# Microcontroller.net
KiCad netlist of a schematic drawn in Altium Designer
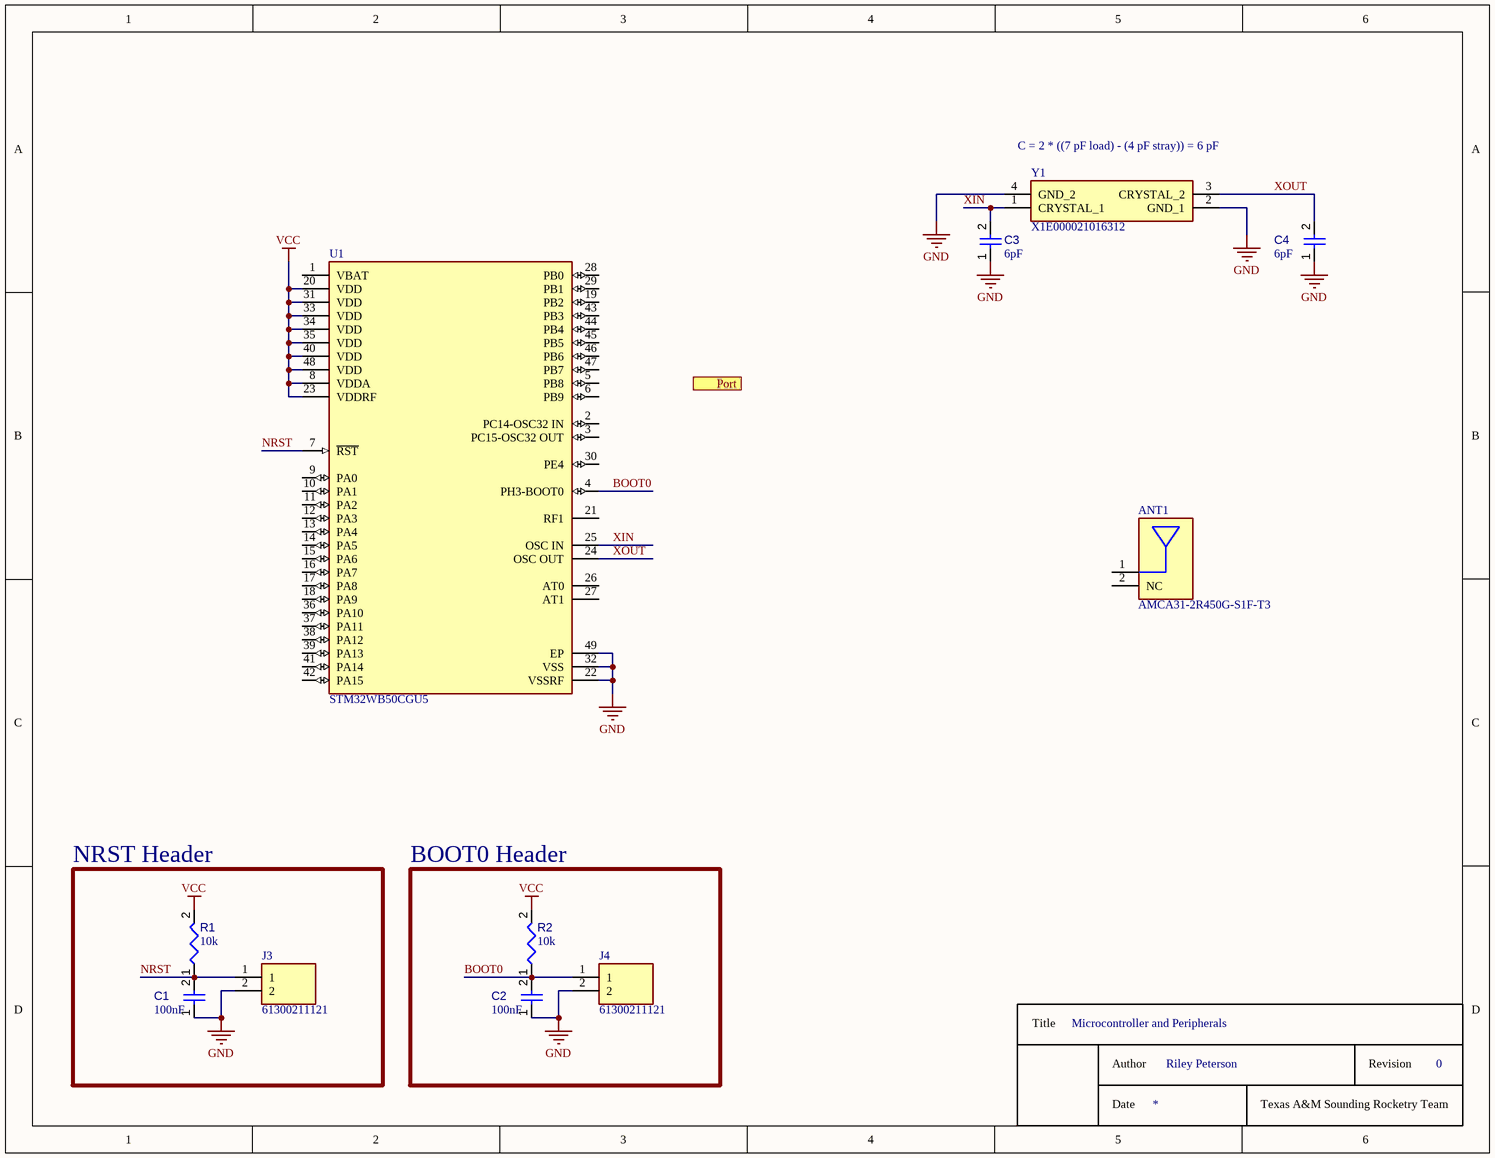
[diagram p0: Microcontroller.SchDoc]

(export (version "E")
  (design (tool "Eeschema 10.0.6"))
  (components
    (comp (ref "ANT1")
      (value "AMCA31-2R450G-S1F-T3")
      (footprint "FP-AMCA31-MFG")
      (description "RF ANT 2.4GHZ CHIP SOLDER SMD")
      (fields
        (field (name "OCTOPART") "https://octopart.com/amca31-2r450g-s1f-t3-abracon-31435383")
        (field (name "MANUFACTURER") "Abracon")
      )
      (libsource (lib "Altium Content Vault") (part "feefd54aed95757a858c12fc87bd8d5"))
    )
    (comp (ref "C1")
      (value "100nF")
      (footprint "CAPC0603(1608)100_L")
      (description "Capacitor")
      (fields (field (name "Comment") "Capacitors,0603,smt,100nF"))
      (libsource (lib "Riley Peterson") (part "CAP-NP-2"))
    )
    (comp (ref "C2")
      (value "100nF")
      (footprint "CAPC0603(1608)100_L")
      (description "Capacitor")
      (fields (field (name "Comment") "Capacitors,0603,smt,100nF"))
      (libsource (lib "Riley Peterson") (part "CAP-NP-2"))
    )
    (comp (ref "C3")
      (value "6pF")
      (footprint "CAPC0603(1608)100_L")
      (description "Capacitor")
      (fields (field (name "Comment") "Capacitors,0603,smt,6pF"))
      (libsource (lib "Riley Peterson") (part "CAP-NP-2"))
    )
    (comp (ref "C4")
      (value "6pF")
      (footprint "CAPC0603(1608)100_L")
      (description "Capacitor")
      (fields (field (name "Comment") "Capacitors,0603,smt,6pF"))
      (libsource (lib "Riley Peterson") (part "CAP-NP-2"))
    )
    (comp (ref "J3")
      (value "61300211121")
      (footprint "SamacSys:HDRV2W110P0X254_1X2_508X254X854P")
      (description "Connector")
      (fields (field (name "MOUSER PART NUMBER") "710-61300211121"))
      (libsource (lib "*") (part "61300211121"))
    )
    (comp (ref "J4")
      (value "61300211121")
      (footprint "SamacSys:HDRV2W110P0X254_1X2_508X254X854P")
      (description "Connector")
      (fields (field (name "MOUSER PART NUMBER") "710-61300211121"))
      (libsource (lib "*") (part "61300211121"))
    )
    (comp (ref "R1")
      (value "10k")
      (footprint "RESC0603(1608)_L")
      (description "Resistor")
      (fields (field (name "Comment") "Resistors,0603,smt,10k"))
      (libsource (lib "Riley Peterson") (part "RES-2"))
    )
    (comp (ref "R2")
      (value "10k")
      (footprint "RESC0603(1608)_L")
      (description "Resistor")
      (fields (field (name "Comment") "Resistors,0603,smt,10k"))
      (libsource (lib "Riley Peterson") (part "RES-2"))
    )
    (comp (ref "U1")
      (value "STM32WB50CGU5")
      (footprint "FP-UFQFPN48-A0B9-MFG")
      (description "ULTRA-LOW-POWER DUAL CORE ARM CO")
      (fields
        (field (name "MANUFACTURER") "STMicroelectronics")
        (field (name "OCTOPART") "https://octopart.com/stm32wb50cgu5-stmicroelectronics-106131324")
      )
      (libsource (lib "Altium Content Vault") (part "0a46fecf8989bdbed877c0c59f49bea"))
    )
    (comp (ref "Y1")
      (value "X1E000021016312")
      (footprint "SamacSys:X1E000021016312")
      (description "Crystal or Oscillator")
      (libsource (lib "*") (part "X1E000021016312"))
    )
  )
  (nets
    (net (code "1") (name "/BOOT0") (class "Default")
      (node (ref "C2") (pin "2") (pinfunction "2_2") (pintype "passive"))
      (node (ref "J4") (pin "1") (pinfunction "1_1") (pintype "passive"))
      (node (ref "R2") (pin "1") (pinfunction "1_1") (pintype "passive"))
      (node (ref "U1") (pin "4") (pinfunction "PH3-BOOT0_4") (pintype "bidirectional"))
    )
    (net (code "2") (name "/NRST") (class "Default")
      (node (ref "C1") (pin "2") (pinfunction "2_2") (pintype "passive"))
      (node (ref "J3") (pin "1") (pinfunction "1_1") (pintype "passive"))
      (node (ref "R1") (pin "1") (pinfunction "1_1") (pintype "passive"))
      (node (ref "U1") (pin "7") (pinfunction "~{RST}_7") (pintype "input"))
    )
    (net (code "4") (name "/XIN") (class "Default")
      (node (ref "C3") (pin "2") (pinfunction "2_2") (pintype "passive"))
      (node (ref "U1") (pin "25") (pinfunction "OSC_IN_25") (pintype "passive"))
      (node (ref "Y1") (pin "1") (pinfunction "CRYSTAL_1_1") (pintype "passive"))
    )
    (net (code "5") (name "/XOUT") (class "Default")
      (node (ref "C4") (pin "2") (pinfunction "2_2") (pintype "passive"))
      (node (ref "U1") (pin "24") (pinfunction "OSC_OUT_24") (pintype "passive"))
      (node (ref "Y1") (pin "3") (pinfunction "CRYSTAL_2_3") (pintype "passive"))
    )
    (net (code "6") (name "GND") (class "Default")
      (node (ref "C1") (pin "1") (pinfunction "1_1") (pintype "passive"))
      (node (ref "C2") (pin "1") (pinfunction "1_1") (pintype "passive"))
      (node (ref "C3") (pin "1") (pinfunction "1_1") (pintype "passive"))
      (node (ref "C4") (pin "1") (pinfunction "1_1") (pintype "passive"))
      (node (ref "J3") (pin "2") (pinfunction "2_2") (pintype "passive"))
      (node (ref "J4") (pin "2") (pinfunction "2_2") (pintype "passive"))
      (node (ref "U1") (pin "22") (pinfunction "VSSRF_22") (pintype "power_in"))
      (node (ref "U1") (pin "32") (pinfunction "VSS_32") (pintype "power_in"))
      (node (ref "U1") (pin "49") (pinfunction "EP_49") (pintype "power_in"))
      (node (ref "Y1") (pin "2") (pinfunction "GND_1_2") (pintype "passive"))
      (node (ref "Y1") (pin "4") (pinfunction "GND_2_4") (pintype "passive"))
    )
    (net (code "7") (name "VCC") (class "Default")
      (node (ref "R1") (pin "2") (pinfunction "2_2") (pintype "passive"))
      (node (ref "R2") (pin "2") (pinfunction "2_2") (pintype "passive"))
      (node (ref "U1") (pin "20") (pinfunction "VDD_20") (pintype "power_in"))
      (node (ref "U1") (pin "23") (pinfunction "VDDRF_23") (pintype "power_in"))
      (node (ref "U1") (pin "31") (pinfunction "VDD_31") (pintype "power_in"))
      (node (ref "U1") (pin "33") (pinfunction "VDD_33") (pintype "power_in"))
      (node (ref "U1") (pin "34") (pinfunction "VDD_34") (pintype "power_in"))
      (node (ref "U1") (pin "35") (pinfunction "VDD_35") (pintype "power_in"))
      (node (ref "U1") (pin "40") (pinfunction "VDD_40") (pintype "power_in"))
      (node (ref "U1") (pin "48") (pinfunction "VDD_48") (pintype "power_in"))
      (node (ref "U1") (pin "8") (pinfunction "VDDA_8") (pintype "power_in"))
    )
    (net (code "8") (name "unconnected-(ANT1-Feed_Point-Pad1)") (class "Default")
      (node (ref "ANT1") (pin "1") (pinfunction "Feed_Point_1") (pintype "passive"))
    )
    (net (code "9") (name "unconnected-(ANT1-NC-Pad2)") (class "Default")
      (node (ref "ANT1") (pin "2") (pinfunction "NC_2") (pintype "passive"))
    )
    (net (code "10") (name "unconnected-(U1-AT0-Pad26)") (class "Default")
      (node (ref "U1") (pin "26") (pinfunction "AT0_26") (pintype "passive"))
    )
    (net (code "11") (name "unconnected-(U1-AT1-Pad27)") (class "Default")
      (node (ref "U1") (pin "27") (pinfunction "AT1_27") (pintype "passive"))
    )
    (net (code "12") (name "unconnected-(U1-PA0-Pad9)") (class "Default")
      (node (ref "U1") (pin "9") (pinfunction "PA0_9") (pintype "bidirectional"))
    )
    (net (code "13") (name "unconnected-(U1-PA1-Pad10)") (class "Default")
      (node (ref "U1") (pin "10") (pinfunction "PA1_10") (pintype "bidirectional"))
    )
    (net (code "14") (name "unconnected-(U1-PA2-Pad11)") (class "Default")
      (node (ref "U1") (pin "11") (pinfunction "PA2_11") (pintype "bidirectional"))
    )
    (net (code "15") (name "unconnected-(U1-PA3-Pad12)") (class "Default")
      (node (ref "U1") (pin "12") (pinfunction "PA3_12") (pintype "bidirectional"))
    )
    (net (code "16") (name "unconnected-(U1-PA4-Pad13)") (class "Default")
      (node (ref "U1") (pin "13") (pinfunction "PA4_13") (pintype "bidirectional"))
    )
    (net (code "17") (name "unconnected-(U1-PA5-Pad14)") (class "Default")
      (node (ref "U1") (pin "14") (pinfunction "PA5_14") (pintype "bidirectional"))
    )
    (net (code "18") (name "unconnected-(U1-PA6-Pad15)") (class "Default")
      (node (ref "U1") (pin "15") (pinfunction "PA6_15") (pintype "bidirectional"))
    )
    (net (code "19") (name "unconnected-(U1-PA7-Pad16)") (class "Default")
      (node (ref "U1") (pin "16") (pinfunction "PA7_16") (pintype "bidirectional"))
    )
    (net (code "20") (name "unconnected-(U1-PA8-Pad17)") (class "Default")
      (node (ref "U1") (pin "17") (pinfunction "PA8_17") (pintype "bidirectional"))
    )
    (net (code "21") (name "unconnected-(U1-PA9-Pad18)") (class "Default")
      (node (ref "U1") (pin "18") (pinfunction "PA9_18") (pintype "bidirectional"))
    )
    (net (code "22") (name "unconnected-(U1-PA10-Pad36)") (class "Default")
      (node (ref "U1") (pin "36") (pinfunction "PA10_36") (pintype "bidirectional"))
    )
    (net (code "23") (name "unconnected-(U1-PA11-Pad37)") (class "Default")
      (node (ref "U1") (pin "37") (pinfunction "PA11_37") (pintype "bidirectional"))
    )
    (net (code "24") (name "unconnected-(U1-PA12-Pad38)") (class "Default")
      (node (ref "U1") (pin "38") (pinfunction "PA12_38") (pintype "bidirectional"))
    )
    (net (code "25") (name "unconnected-(U1-PA13-Pad39)") (class "Default")
      (node (ref "U1") (pin "39") (pinfunction "PA13_39") (pintype "bidirectional"))
    )
    (net (code "26") (name "unconnected-(U1-PA14-Pad41)") (class "Default")
      (node (ref "U1") (pin "41") (pinfunction "PA14_41") (pintype "bidirectional"))
    )
    (net (code "27") (name "unconnected-(U1-PA15-Pad42)") (class "Default")
      (node (ref "U1") (pin "42") (pinfunction "PA15_42") (pintype "bidirectional"))
    )
    (net (code "28") (name "unconnected-(U1-PB0-Pad28)") (class "Default")
      (node (ref "U1") (pin "28") (pinfunction "PB0_28") (pintype "bidirectional"))
    )
    (net (code "29") (name "unconnected-(U1-PB1-Pad29)") (class "Default")
      (node (ref "U1") (pin "29") (pinfunction "PB1_29") (pintype "bidirectional"))
    )
    (net (code "30") (name "unconnected-(U1-PB2-Pad19)") (class "Default")
      (node (ref "U1") (pin "19") (pinfunction "PB2_19") (pintype "bidirectional"))
    )
    (net (code "31") (name "unconnected-(U1-PB3-Pad43)") (class "Default")
      (node (ref "U1") (pin "43") (pinfunction "PB3_43") (pintype "bidirectional"))
    )
    (net (code "32") (name "unconnected-(U1-PB4-Pad44)") (class "Default")
      (node (ref "U1") (pin "44") (pinfunction "PB4_44") (pintype "bidirectional"))
    )
    (net (code "33") (name "unconnected-(U1-PB5-Pad45)") (class "Default")
      (node (ref "U1") (pin "45") (pinfunction "PB5_45") (pintype "bidirectional"))
    )
    (net (code "34") (name "unconnected-(U1-PB6-Pad46)") (class "Default")
      (node (ref "U1") (pin "46") (pinfunction "PB6_46") (pintype "bidirectional"))
    )
    (net (code "35") (name "unconnected-(U1-PB7-Pad47)") (class "Default")
      (node (ref "U1") (pin "47") (pinfunction "PB7_47") (pintype "bidirectional"))
    )
    (net (code "36") (name "unconnected-(U1-PB8-Pad5)") (class "Default")
      (node (ref "U1") (pin "5") (pinfunction "PB8_5") (pintype "bidirectional"))
    )
    (net (code "37") (name "unconnected-(U1-PB9-Pad6)") (class "Default")
      (node (ref "U1") (pin "6") (pinfunction "PB9_6") (pintype "bidirectional"))
    )
    (net (code "38") (name "unconnected-(U1-PC14-OSC32_IN-Pad2)") (class "Default")
      (node (ref "U1") (pin "2") (pinfunction "PC14-OSC32_IN_2") (pintype "bidirectional"))
    )
    (net (code "39") (name "unconnected-(U1-PC15-OSC32_OUT-Pad3)") (class "Default")
      (node (ref "U1") (pin "3") (pinfunction "PC15-OSC32_OUT_3") (pintype "bidirectional"))
    )
    (net (code "40") (name "unconnected-(U1-PE4-Pad30)") (class "Default")
      (node (ref "U1") (pin "30") (pinfunction "PE4_30") (pintype "bidirectional"))
    )
    (net (code "41") (name "unconnected-(U1-RF1-Pad21)") (class "Default")
      (node (ref "U1") (pin "21") (pinfunction "RF1_21") (pintype "passive"))
    )
    (net (code "42") (name "unconnected-(U1-VBAT-Pad1)") (class "Default")
      (node (ref "U1") (pin "1") (pinfunction "VBAT_1") (pintype "power_in"))
    )
  )
)
